# Pump.net
KiCad netlist of a schematic drawn in Altium Designer
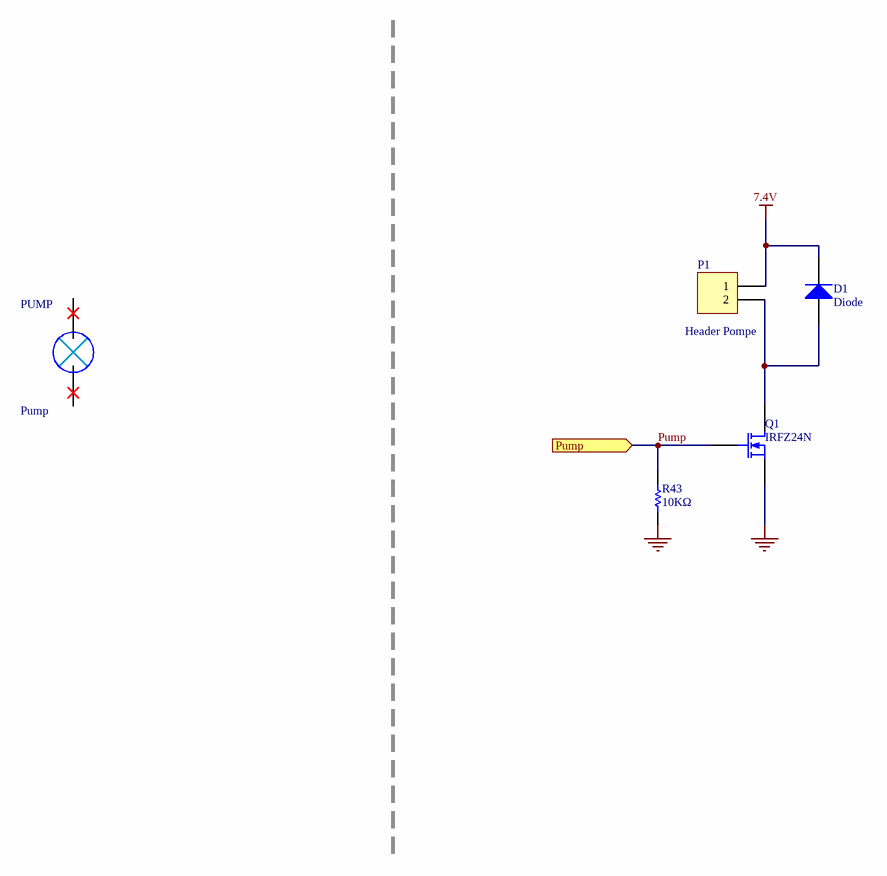
[diagram p0: Pump.SchDoc]

(export (version "E")
  (design (tool "Eeschema 10.0.6"))
  (components
    (comp (ref "D1")
      (value "Diode")
      (footprint "SMC")
      (fields (field (name "PUBLISHER") "Altium Limited"))
      (libsource (lib "Miscellaneous Devices") (part "Diode"))
    )
    (comp (ref "P1")
      (value "Header Pompe")
      (footprint "BORNIER")
      (description "Header, 2-Pin")
      (fields
        (field (name "MANUFACTURER") "BUCHANAN - TE CONNECTIVITY")
        (field (name "PUBLISHER") "Altium Limited")
      )
      (libsource (lib "Miscellaneous Connectors") (part "Header 2"))
    )
    (comp (ref "PUMP")
      (value "Pump")
      (fields (field (name "MANUFACTURER") "/"))
      (libsource (lib "Electroplant") (part "Pump"))
    )
    (comp (ref "Q1")
      (value "IRFZ24N")
      (footprint "E3")
      (description "N-Channel MOSFET")
      (fields (field (name "MANUFACTURER") "INFINEON") (field (name "PUBLISHER") "Altium Limited"))
      (libsource (lib "Miscellaneous Devices") (part "MOSFET-N"))
    )
    (comp (ref "R43")
      (value "10KΩ")
      (footprint "R0603")
      (description "Resistor")
      (fields (field (name "MANUFACTURER") "MULTICOMP") (field (name "PUBLISHER") "Altium Limited"))
      (libsource (lib "Miscellaneous Devices") (part "Res1"))
    )
  )
  (nets
    (net (code "1") (name "/Pump") (class "Default")
      (node (ref "Q1") (pin "2") (pinfunction "G_2") (pintype "passive"))
      (node (ref "R43") (pin "1") (pinfunction "1_1") (pintype "passive"))
    )
    (net (code "2") (name "7.4V") (class "Default")
      (node (ref "D1") (pin "2") (pinfunction "K_2") (pintype "passive"))
      (node (ref "P1") (pin "1") (pinfunction "1_1") (pintype "passive"))
    )
    (net (code "3") (name "GND") (class "Default")
      (node (ref "Q1") (pin "3") (pinfunction "S_3") (pintype "passive"))
      (node (ref "R43") (pin "2") (pinfunction "2_2") (pintype "passive"))
    )
    (net (code "4") (name "Net-(D1-A)") (class "Default")
      (node (ref "D1") (pin "1") (pinfunction "A_1") (pintype "passive"))
      (node (ref "P1") (pin "2") (pinfunction "2_2") (pintype "passive"))
      (node (ref "Q1") (pin "1") (pinfunction "D_1") (pintype "passive"))
    )
    (net (code "5") (name "unconnected-(PUMP-Pad1)") (class "Default")
      (node (ref "PUMP") (pin "1") (pinfunction "1_1") (pintype "passive"))
    )
    (net (code "6") (name "unconnected-(PUMP-Pad2)") (class "Default")
      (node (ref "PUMP") (pin "2") (pinfunction "2_2") (pintype "passive"))
    )
  )
)
